# AuxilaryWiring.net
KiCad netlist of a schematic drawn in EAGLE
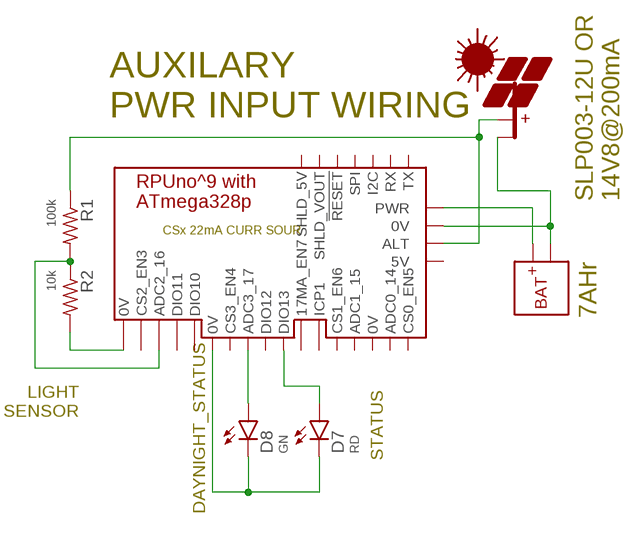
[diagram p0: schematic, sheet 1]

(export (version "E")
  (design (tool "Eeschema 10.0.6"))
  (components
    (comp (ref "BM1")
      (value "RPUNO")
      (footprint "eagle-import:NA-30")
      (libsource (lib "eagle-import") (part "RPUNO"))
    )
    (comp (ref "D7")
      (value "RD")
      (footprint "eagle-import:LED5MM")
      (libsource (lib "eagle-import") (part "LED5MM"))
    )
    (comp (ref "D8")
      (value "GN")
      (footprint "eagle-import:LED5MM")
      (libsource (lib "eagle-import") (part "LED5MM"))
    )
    (comp (ref "PV4")
      (value "PV")
      (footprint "eagle-import:NA-30")
      (libsource (lib "eagle-import") (part "PV"))
    )
    (comp (ref "R1")
      (value "100k")
      (footprint "eagle-import:C0805(2012)")
      (libsource (lib "eagle-import") (part "R0805"))
    )
    (comp (ref "R2")
      (value "10k")
      (footprint "eagle-import:C0805(2012)")
      (libsource (lib "eagle-import") (part "R0805"))
    )
    (comp (ref "U$7")
      (value "BAT")
      (footprint "eagle-import:NA-30")
      (libsource (lib "eagle-import") (part "BAT"))
    )
  )
  (nets
    (net (code "1") (name "Net-(BM1-0V-Pad27)") (class "Default")
      (node (ref "BM1") (pin "27") (pinfunction "0V_27") (pintype "bidirectional"))
      (node (ref "R2") (pin "2") (pinfunction "2_2") (pintype "passive"))
    )
    (net (code "2") (name "Net-(BM1-0V-Pad28)") (class "Default")
      (node (ref "BM1") (pin "28") (pinfunction "0V_28") (pintype "bidirectional"))
      (node (ref "D7") (pin "K") (pinfunction "K_K") (pintype "passive"))
      (node (ref "D8") (pin "K") (pinfunction "K_K") (pintype "passive"))
    )
    (net (code "3") (name "Net-(BM1-ADC2_16)") (class "Default")
      (node (ref "BM1") (pin "13") (pinfunction "ADC2_16_13") (pintype "bidirectional"))
      (node (ref "R1") (pin "2") (pinfunction "2_2") (pintype "passive"))
      (node (ref "R2") (pin "1") (pinfunction "1_1") (pintype "passive"))
    )
    (net (code "4") (name "Net-(BM1-ADC3_17)") (class "Default")
      (node (ref "BM1") (pin "16") (pinfunction "ADC3_17_16") (pintype "bidirectional"))
      (node (ref "D8") (pin "A") (pinfunction "A_A") (pintype "passive"))
    )
    (net (code "5") (name "Net-(BM1-ALT)") (class "Default")
      (node (ref "BM1") (pin "20") (pinfunction "ALT_20") (pintype "bidirectional"))
      (node (ref "PV4") (pin "1") (pinfunction "+PV_1") (pintype "bidirectional"))
      (node (ref "R1") (pin "1") (pinfunction "1_1") (pintype "passive"))
    )
    (net (code "6") (name "Net-(BM1-DIO13)") (class "Default")
      (node (ref "BM1") (pin "18") (pinfunction "DIO13_18") (pintype "bidirectional"))
      (node (ref "D7") (pin "A") (pinfunction "A_A") (pintype "passive"))
    )
    (net (code "7") (name "Net-(BM1-PWR)") (class "Default")
      (node (ref "BM1") (pin "8") (pinfunction "PWR_8") (pintype "bidirectional"))
      (node (ref "U$7") (pin "1") (pinfunction "+BAT_1") (pintype "bidirectional"))
    )
    (net (code "8") (name "Net-(PV4--PV)") (class "Default")
      (node (ref "BM1") (pin "9") (pinfunction "0V_9") (pintype "bidirectional"))
      (node (ref "PV4") (pin "2") (pinfunction "-PV_2") (pintype "bidirectional"))
      (node (ref "U$7") (pin "2") (pinfunction "-BAT_2") (pintype "bidirectional"))
    )
    (net (code "9") (name "unconnected-(BM1-0V-Pad26)") (class "Default")
      (node (ref "BM1") (pin "26") (pinfunction "0V_26") (pintype "bidirectional"))
    )
    (net (code "10") (name "unconnected-(BM1-5V-Pad19)") (class "Default")
      (node (ref "BM1") (pin "19") (pinfunction "5V_19") (pintype "bidirectional"))
    )
    (net (code "11") (name "unconnected-(BM1-17MA_EN7-Pad21)") (class "Default")
      (node (ref "BM1") (pin "21") (pinfunction "17MA_EN7_21") (pintype "bidirectional"))
    )
    (net (code "12") (name "unconnected-(BM1-ADC0_14-Pad11)") (class "Default")
      (node (ref "BM1") (pin "11") (pinfunction "ADC0_14_11") (pintype "bidirectional"))
    )
    (net (code "13") (name "unconnected-(BM1-ADC1_15-Pad10)") (class "Default")
      (node (ref "BM1") (pin "10") (pinfunction "ADC1_15_10") (pintype "bidirectional"))
    )
    (net (code "14") (name "unconnected-(BM1-CS0_EN5-Pad23)") (class "Default")
      (node (ref "BM1") (pin "23") (pinfunction "CS0_EN5_23") (pintype "bidirectional"))
    )
    (net (code "15") (name "unconnected-(BM1-CS1_EN6-Pad22)") (class "Default")
      (node (ref "BM1") (pin "22") (pinfunction "CS1_EN6_22") (pintype "bidirectional"))
    )
    (net (code "16") (name "unconnected-(BM1-CS2_EN3-Pad24)") (class "Default")
      (node (ref "BM1") (pin "24") (pinfunction "CS2_EN3_24") (pintype "bidirectional"))
    )
    (net (code "17") (name "unconnected-(BM1-CS3_EN4-Pad29)") (class "Default")
      (node (ref "BM1") (pin "29") (pinfunction "CS3_EN4_29") (pintype "bidirectional"))
    )
    (net (code "18") (name "unconnected-(BM1-DIO10-Pad15)") (class "Default")
      (node (ref "BM1") (pin "15") (pinfunction "DIO10_15") (pintype "bidirectional"))
    )
    (net (code "19") (name "unconnected-(BM1-DIO11-Pad14)") (class "Default")
      (node (ref "BM1") (pin "14") (pinfunction "DIO11_14") (pintype "bidirectional"))
    )
    (net (code "20") (name "unconnected-(BM1-DIO12-Pad17)") (class "Default")
      (node (ref "BM1") (pin "17") (pinfunction "DIO12_17") (pintype "bidirectional"))
    )
    (net (code "21") (name "unconnected-(BM1-I2C-Pad3)") (class "Default")
      (node (ref "BM1") (pin "3") (pinfunction "I2C_3") (pintype "bidirectional"))
    )
    (net (code "22") (name "unconnected-(BM1-ICP1-Pad12)") (class "Default")
      (node (ref "BM1") (pin "12") (pinfunction "ICP1_12") (pintype "bidirectional"))
    )
    (net (code "23") (name "unconnected-(BM1-RX-Pad2)") (class "Default")
      (node (ref "BM1") (pin "2") (pinfunction "RX_2") (pintype "bidirectional"))
    )
    (net (code "24") (name "unconnected-(BM1-SHLD_5V-Pad6)") (class "Default")
      (node (ref "BM1") (pin "6") (pinfunction "SHLD_5V_6") (pintype "bidirectional"))
    )
    (net (code "25") (name "unconnected-(BM1-SHLD_VOUT-Pad7)") (class "Default")
      (node (ref "BM1") (pin "7") (pinfunction "SHLD_VOUT_7") (pintype "bidirectional"))
    )
    (net (code "26") (name "unconnected-(BM1-SPI-Pad4)") (class "Default")
      (node (ref "BM1") (pin "4") (pinfunction "SPI_4") (pintype "bidirectional"))
    )
    (net (code "27") (name "unconnected-(BM1-TX-Pad1)") (class "Default")
      (node (ref "BM1") (pin "1") (pinfunction "TX_1") (pintype "bidirectional"))
    )
    (net (code "28") (name "unconnected-(BM1-~{RESET}-Pad5)") (class "Default")
      (node (ref "BM1") (pin "5") (pinfunction "~{RESET}_5") (pintype "bidirectional"))
    )
  )
)
